# Control_Pilot_Schem.net
KiCad netlist of a schematic drawn in Altium Designer
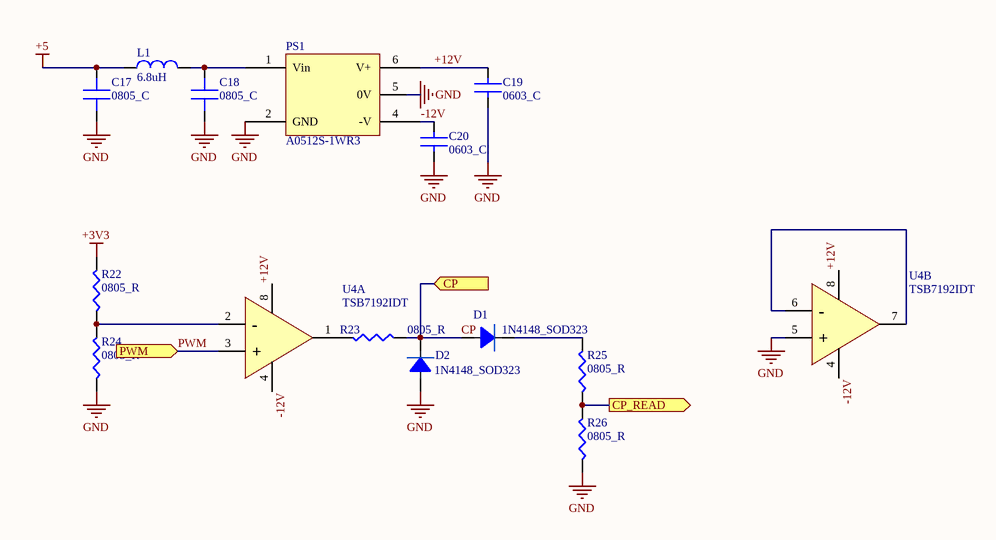
[diagram p0: Control_Pilot_Schem.SchDoc]

(export (version "E")
  (design (tool "Eeschema 10.0.6"))
  (components
    (comp (ref "C17")
      (value "0805_C")
      (footprint "C0805 - 0.1uf")
      (description "0805 Capacitor")
      (libsource (lib "TimerSMD_Components") (part "0805 Capacitor"))
    )
    (comp (ref "C18")
      (value "0805_C")
      (footprint "C0805 - 0.1uf")
      (description "0805 Capacitor")
      (libsource (lib "TimerSMD_Components") (part "0805 Capacitor"))
    )
    (comp (ref "C19")
      (value "0603_C")
      (footprint "0603_CAP")
      (libsource (lib "TimerSMD_Components") (part "0603 Capacitor"))
    )
    (comp (ref "C20")
      (value "0603_C")
      (footprint "0603_CAP")
      (libsource (lib "TimerSMD_Components") (part "0603 Capacitor"))
    )
    (comp (ref "D1")
      (value "1N4148_SOD323")
      (footprint "SOD-323")
      (description "DIODE GEN PURP 100V 300MA SOD123")
      (fields (field (name "VOLTAGE") "100V"))
      (libsource (lib "TimerSMD_Components") (part "1N4148WS"))
    )
    (comp (ref "D2")
      (value "1N4148_SOD323")
      (footprint "SOD-323")
      (description "DIODE GEN PURP 100V 300MA SOD123")
      (fields (field (name "VOLTAGE") "100V"))
      (libsource (lib "TimerSMD_Components") (part "1N4148WS"))
    )
    (comp (ref "L1")
      (value "6.8uH")
      (footprint "R0805")
      (description "6.8uH 0805 Inductor")
      (fields (field (name "TOLERANCE") "10%"))
      (libsource (lib "TimerSMD_Components") (part "ILSB1206ER100K"))
    )
    (comp (ref "PS1")
      (value "A0512S-1WR3")
      (footprint "CONV_RB-0512D/HP")
      (libsource (lib "EV_Symbols") (part "A0512S-1WR3"))
    )
    (comp (ref "R22")
      (value "0805_R")
      (footprint "R0805")
      (libsource (lib "TimerSMD_Components") (part "0805 Resistor"))
    )
    (comp (ref "R23")
      (value "0805_R")
      (footprint "R0805")
      (libsource (lib "TimerSMD_Components") (part "0805 Resistor"))
    )
    (comp (ref "R24")
      (value "0805_R")
      (footprint "R0805")
      (libsource (lib "TimerSMD_Components") (part "0805 Resistor"))
    )
    (comp (ref "R25")
      (value "0805_R")
      (footprint "R0805")
      (libsource (lib "TimerSMD_Components") (part "0805 Resistor"))
    )
    (comp (ref "R26")
      (value "0805_R")
      (footprint "R0805")
      (libsource (lib "TimerSMD_Components") (part "0805 Resistor"))
    )
    (comp (ref "U4")
      (value "TSB7192IDT")
      (footprint "SOP8")
      (description "22MHz 300nA Dual channel SOIC-8 Precision Op Amps ROHS")
      (libsource (lib "EV_Symbols") (part "TSB7192IDT"))
    )
  )
  (nets
    (net (code "1") (name "+3V3") (class "Default")
      (node (ref "R22") (pin "2") (pinfunction "2_2") (pintype "passive"))
    )
    (net (code "2") (name "+5") (class "Default")
      (node (ref "C17") (pin "2") (pinfunction "2_2") (pintype "passive"))
      (node (ref "L1") (pin "1") (pinfunction "1_1") (pintype "passive"))
    )
    (net (code "3") (name "/+12V") (class "Default")
      (node (ref "C19") (pin "1") (pinfunction "1_1") (pintype "passive"))
      (node (ref "PS1") (pin "6") (pinfunction "V+_6") (pintype "passive"))
      (node (ref "U4") (pin "8") (pinfunction "VCC_8") (pintype "passive"))
    )
    (net (code "4") (name "/-12V") (class "Default")
      (node (ref "C20") (pin "1") (pinfunction "1_1") (pintype "passive"))
      (node (ref "PS1") (pin "4") (pinfunction "-V_4") (pintype "passive"))
      (node (ref "U4") (pin "4") (pinfunction "VSS_4") (pintype "passive"))
    )
    (net (code "5") (name "/CP") (class "Default")
      (node (ref "D1") (pin "A") (pinfunction "Anode_A") (pintype "passive"))
      (node (ref "D2") (pin "K") (pinfunction "Cathode_K") (pintype "passive"))
      (node (ref "R23") (pin "1") (pinfunction "1_1") (pintype "passive"))
    )
    (net (code "6") (name "/CP_READ") (class "Default")
      (node (ref "R25") (pin "1") (pinfunction "1_1") (pintype "passive"))
      (node (ref "R26") (pin "2") (pinfunction "2_2") (pintype "passive"))
    )
    (net (code "7") (name "/PWM") (class "Default")
      (node (ref "U4") (pin "3") (pinfunction "+_3") (pintype "passive"))
    )
    (net (code "8") (name "GND") (class "Default")
      (node (ref "C17") (pin "1") (pinfunction "1_1") (pintype "passive"))
      (node (ref "C18") (pin "1") (pinfunction "1_1") (pintype "passive"))
      (node (ref "C19") (pin "2") (pinfunction "2_2") (pintype "passive"))
      (node (ref "C20") (pin "2") (pinfunction "2_2") (pintype "passive"))
      (node (ref "D2") (pin "A") (pinfunction "Anode_A") (pintype "passive"))
      (node (ref "PS1") (pin "2") (pinfunction "GND_2") (pintype "passive"))
      (node (ref "PS1") (pin "5") (pinfunction "0V_5") (pintype "passive"))
      (node (ref "R24") (pin "1") (pinfunction "1_1") (pintype "passive"))
      (node (ref "R26") (pin "1") (pinfunction "1_1") (pintype "passive"))
      (node (ref "U4") (pin "5") (pinfunction "+_5") (pintype "passive"))
    )
    (net (code "9") (name "Net-(D1-Cathode)") (class "Default")
      (node (ref "D1") (pin "K") (pinfunction "Cathode_K") (pintype "passive"))
      (node (ref "R25") (pin "2") (pinfunction "2_2") (pintype "passive"))
    )
    (net (code "10") (name "Net-(PS1-Vin)") (class "Default")
      (node (ref "C18") (pin "2") (pinfunction "2_2") (pintype "passive"))
      (node (ref "L1") (pin "2") (pinfunction "2_2") (pintype "passive"))
      (node (ref "PS1") (pin "1") (pinfunction "Vin_1") (pintype "passive"))
    )
    (net (code "11") (name "Net-(U4A--)") (class "Default")
      (node (ref "R22") (pin "1") (pinfunction "1_1") (pintype "passive"))
      (node (ref "R24") (pin "2") (pinfunction "2_2") (pintype "passive"))
      (node (ref "U4") (pin "2") (pinfunction "-_2") (pintype "passive"))
    )
    (net (code "12") (name "Net-(U4A-OUT1)") (class "Default")
      (node (ref "R23") (pin "2") (pinfunction "2_2") (pintype "passive"))
      (node (ref "U4") (pin "1") (pinfunction "OUT1_1") (pintype "passive"))
    )
    (net (code "13") (name "Net-(U4B--)") (class "Default")
      (node (ref "U4") (pin "6") (pinfunction "-_6") (pintype "passive"))
      (node (ref "U4") (pin "7") (pinfunction "OUT1_7") (pintype "passive"))
    )
  )
)
